# femtoUSB_r1_0_2-rgb.net
KiCad netlist of a schematic drawn in EAGLE
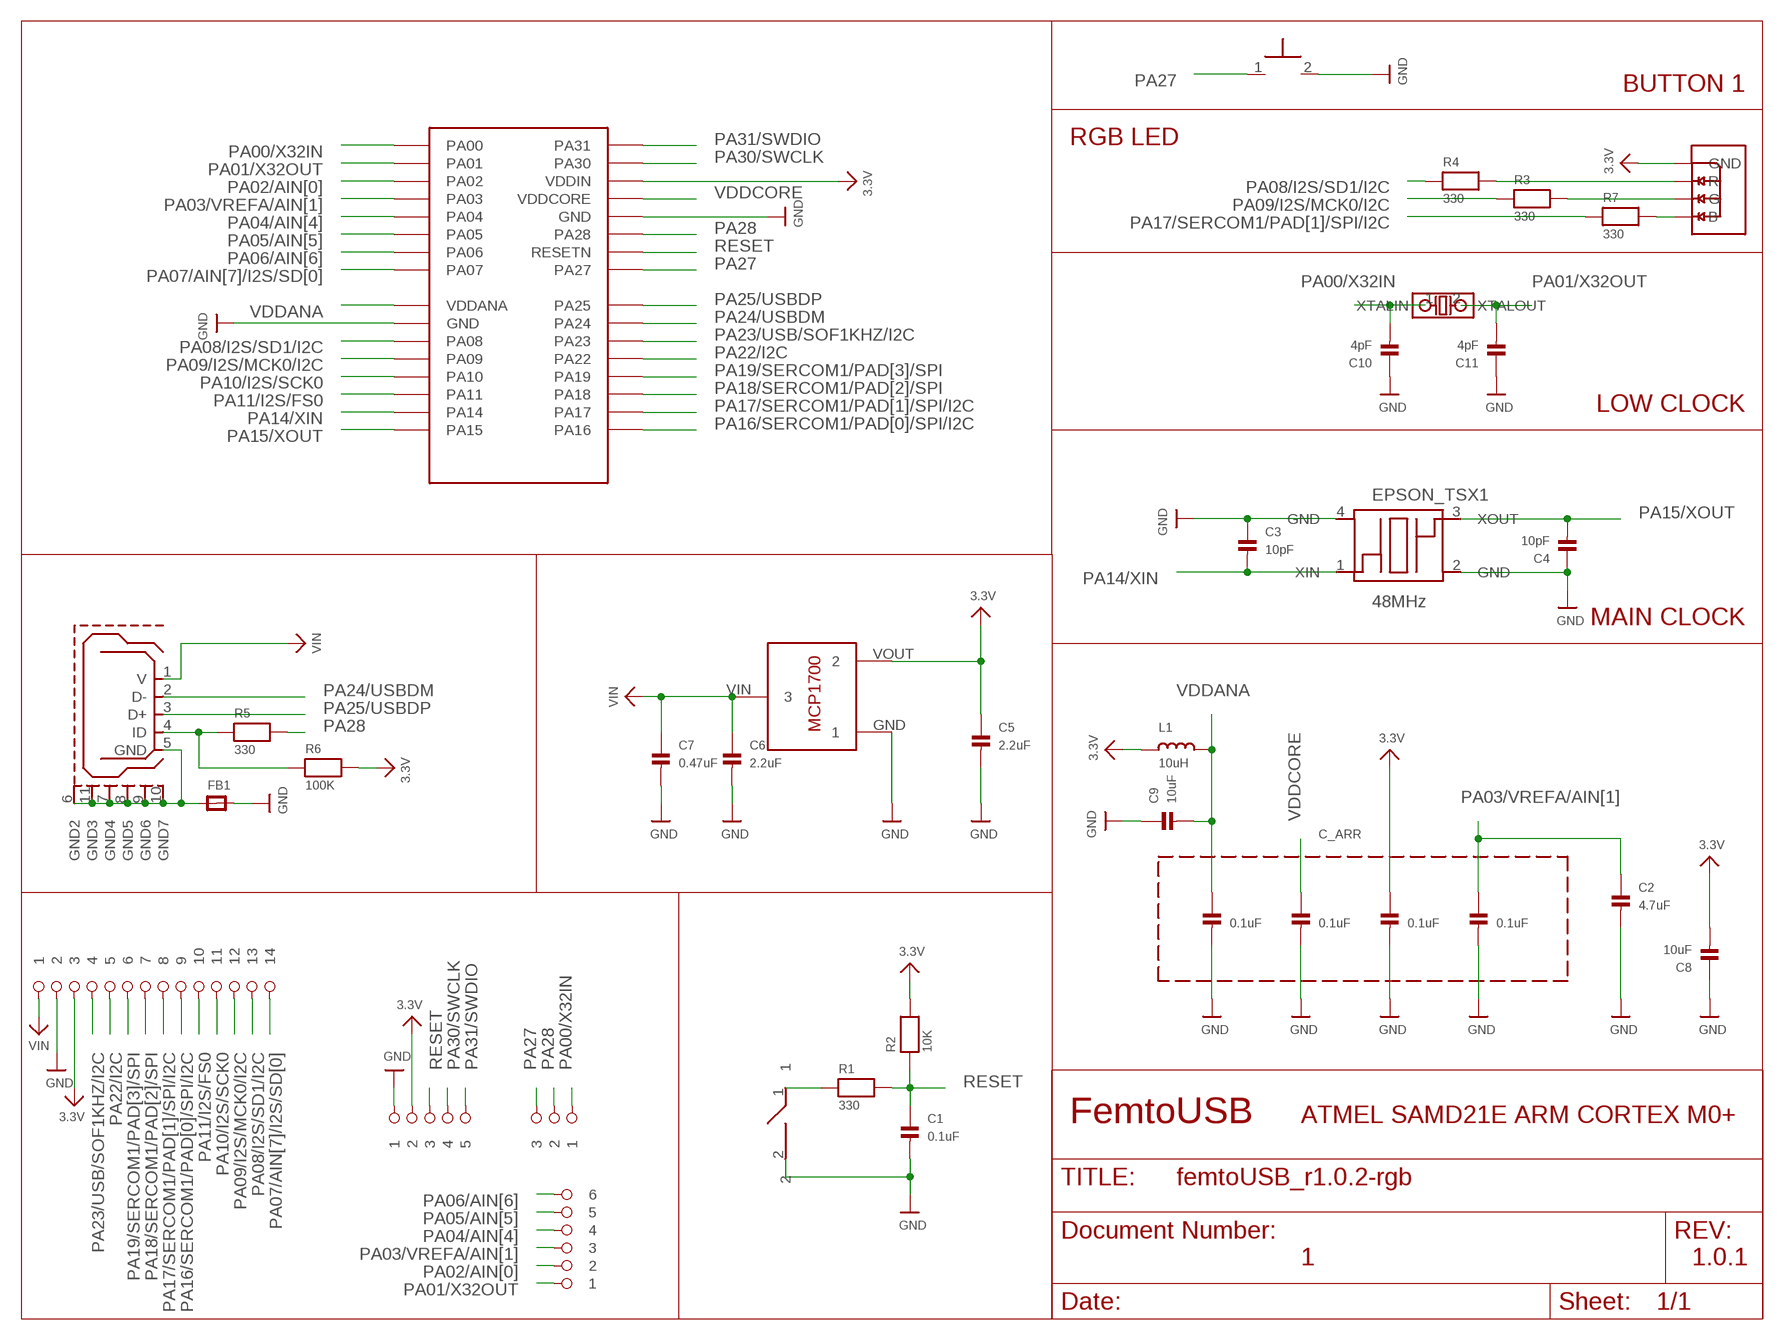
[diagram p0: schematic, sheet 1]

(export (version "E")
  (design (tool "Eeschema 10.0.6"))
  (components
    (comp (ref "BTN_BOOT")
      (value "TACTILE_SWITCH_NO_GND_NO_BOSS")
      (footprint "eagle-import:SIDE_ACT_NO_GND_NO_BOSS")
      (libsource (lib "eagle-import") (part "TACTILE_SWITCH_NO_GND_NO_BOSS"))
    )
    (comp (ref "C1")
      (value "0.1uF")
      (footprint "eagle-import:_0402MP")
      (libsource (lib "eagle-import") (part "CAP_CERAMIC_0402MP"))
    )
    (comp (ref "C2")
      (value "4.7uF")
      (footprint "eagle-import:_0402MP")
      (libsource (lib "eagle-import") (part "CAP_CERAMIC_0402MP"))
    )
    (comp (ref "C3")
      (value "10pF")
      (footprint "eagle-import:_0402MP")
      (libsource (lib "eagle-import") (part "CAP_CERAMIC_0402MP"))
    )
    (comp (ref "C4")
      (value "10pF")
      (footprint "eagle-import:_0402MP")
      (libsource (lib "eagle-import") (part "CAP_CERAMIC_0402MP"))
    )
    (comp (ref "C5")
      (value "2.2uF")
      (footprint "eagle-import:_0402MP")
      (libsource (lib "eagle-import") (part "CAP_CERAMIC_0402MP"))
    )
    (comp (ref "C6")
      (value "2.2uF")
      (footprint "eagle-import:_0402MP")
      (libsource (lib "eagle-import") (part "CAP_CERAMIC_0402MP"))
    )
    (comp (ref "C7")
      (value "0.47uF")
      (footprint "eagle-import:_0402MP")
      (libsource (lib "eagle-import") (part "CAP_CERAMIC_0402MP"))
    )
    (comp (ref "C8")
      (value "10uF")
      (footprint "eagle-import:_0402MP")
      (libsource (lib "eagle-import") (part "CAP_CERAMIC_0402MP"))
    )
    (comp (ref "C9")
      (value "10uF")
      (footprint "eagle-import:_0402MP")
      (libsource (lib "eagle-import") (part "CAP_CERAMIC_0402MP"))
    )
    (comp (ref "C10")
      (value "4pF")
      (footprint "eagle-import:_0402MP")
      (libsource (lib "eagle-import") (part "CAP_CERAMIC_0402MP"))
    )
    (comp (ref "C11")
      (value "4pF")
      (footprint "eagle-import:_0402MP")
      (libsource (lib "eagle-import") (part "CAP_CERAMIC_0402MP"))
    )
    (comp (ref "C_ARR")
      (value "0.1uF")
      (footprint "eagle-import:CAPACITOR_ARRAY_1206_MONO_1X4")
      (libsource (lib "eagle-import") (part "KEMET_CERAMIC_CAPACITOR_ARRAY_1X4"))
    )
    (comp (ref "EPSON_TSX1")
      (value "48MHz")
      (footprint "eagle-import:TSX-3225")
      (libsource (lib "eagle-import") (part "TSX-3225"))
    )
    (comp (ref "FB1")
      (value "FERRITE_0603MP")
      (footprint "eagle-import:_0603MP")
      (libsource (lib "eagle-import") (part "FERRITE_0603MP"))
    )
    (comp (ref "IC1")
      (value "ATSAMD21E18A-MUT")
      (footprint "eagle-import:QFN32")
      (libsource (lib "eagle-import") (part "ATSAMD21E18A-MUT"))
    )
    (comp (ref "L1")
      (value "10uH")
      (footprint "eagle-import:_0603MP")
      (libsource (lib "eagle-import") (part "INDUCTOR_0603MP"))
    )
    (comp (ref "LDO_VREG")
      (value "MCP1700T-3302E/TT")
      (footprint "eagle-import:MCP1700T-3302E_TT")
      (libsource (lib "eagle-import") (part "MCP1700T-3302E/TT"))
    )
    (comp (ref "MICRO_B_USB")
      (value "USB_MICROB")
      (footprint "eagle-import:USB_MICROB_PACKAGE")
      (libsource (lib "eagle-import") (part "USB_MICROB"))
    )
    (comp (ref "OSC32K")
      (value "ABS06-107-32.768KHZ-T")
      (footprint "eagle-import:ABS06-107-32.768KHZ-T")
      (libsource (lib "eagle-import") (part "ABS06-107-32.768KHZ-T"))
    )
    (comp (ref "PIN_1X3")
      (value "1X3_ROUND")
      (footprint "eagle-import:1X3_ROUND")
      (libsource (lib "eagle-import") (part "1X3_ROUND"))
    )
    (comp (ref "PIN_1X5")
      (value "1X5_ROUND")
      (footprint "eagle-import:1X5_ROUND")
      (libsource (lib "eagle-import") (part "1X5_ROUND"))
    )
    (comp (ref "PIN_1X6")
      (value "1X6_ROUND")
      (footprint "eagle-import:1X6_ROUND")
      (libsource (lib "eagle-import") (part "1X6_ROUND"))
    )
    (comp (ref "PIN_1X14")
      (value "1X14_ROUND")
      (footprint "eagle-import:1X14_ROUND")
      (libsource (lib "eagle-import") (part "1X14_ROUND"))
    )
    (comp (ref "R1")
      (value "330")
      (footprint "eagle-import:_0402MP")
      (libsource (lib "eagle-import") (part "RESISTOR_0402MP"))
    )
    (comp (ref "R2")
      (value "10K")
      (footprint "eagle-import:_0402MP")
      (libsource (lib "eagle-import") (part "RESISTOR_0402MP"))
    )
    (comp (ref "R3")
      (value "330")
      (footprint "eagle-import:_0402MP")
      (libsource (lib "eagle-import") (part "RESISTOR_0402MP"))
    )
    (comp (ref "R4")
      (value "330")
      (footprint "eagle-import:_0402MP")
      (libsource (lib "eagle-import") (part "RESISTOR_0402MP"))
    )
    (comp (ref "R5")
      (value "330")
      (footprint "eagle-import:_0402MP")
      (libsource (lib "eagle-import") (part "RESISTOR_0402MP"))
    )
    (comp (ref "R6")
      (value "100K")
      (footprint "eagle-import:_0402MP")
      (libsource (lib "eagle-import") (part "RESISTOR_0402MP"))
    )
    (comp (ref "R7")
      (value "330")
      (footprint "eagle-import:_0402MP")
      (libsource (lib "eagle-import") (part "RESISTOR_0402MP"))
    )
    (comp (ref "RGBLED")
      (value "LRTB_R48G")
      (footprint "eagle-import:LRTB_R48G")
      (libsource (lib "eagle-import") (part "LRTB_R48G"))
    )
    (comp (ref "SJ_RESET")
      (value "SPST_SMD")
      (footprint "eagle-import:SPST_SMD")
      (libsource (lib "eagle-import") (part "SPST_SMD"))
    )
  )
  (nets
    (net (code "1") (name "/PA00{slash}X32IN") (class "Default")
      (node (ref "C10") (pin "2") (pinfunction "P$2_2") (pintype "passive"))
      (node (ref "IC1") (pin "1") (pinfunction "PA00_1") (pintype "bidirectional"))
      (node (ref "OSC32K") (pin "1") (pinfunction "XTALIN_1") (pintype "bidirectional"))
      (node (ref "PIN_1X3") (pin "P$1") (pinfunction "1_P$1") (pintype "bidirectional"))
    )
    (net (code "2") (name "/PA01{slash}X32OUT") (class "Default")
      (node (ref "C11") (pin "2") (pinfunction "P$2_2") (pintype "passive"))
      (node (ref "IC1") (pin "2") (pinfunction "PA01_2") (pintype "bidirectional"))
      (node (ref "OSC32K") (pin "2") (pinfunction "XTALOUT_2") (pintype "bidirectional"))
      (node (ref "PIN_1X6") (pin "P$1") (pinfunction "1_P$1") (pintype "bidirectional"))
    )
    (net (code "3") (name "/PA02{slash}AIN[0]") (class "Default")
      (node (ref "IC1") (pin "3") (pinfunction "PA02_3") (pintype "bidirectional"))
      (node (ref "PIN_1X6") (pin "P$2") (pinfunction "2_P$2") (pintype "bidirectional"))
    )
    (net (code "4") (name "/PA03{slash}VREFA{slash}AIN[1]") (class "Default")
      (node (ref "C2") (pin "1") (pinfunction "P$1_1") (pintype "passive"))
      (node (ref "C_ARR") (pin "7") (pinfunction "P$7_7") (pintype "passive"))
      (node (ref "IC1") (pin "4") (pinfunction "PA03_4") (pintype "bidirectional"))
      (node (ref "PIN_1X6") (pin "P$3") (pinfunction "3_P$3") (pintype "bidirectional"))
    )
    (net (code "5") (name "/PA04{slash}AIN[4]") (class "Default")
      (node (ref "IC1") (pin "5") (pinfunction "PA04_5") (pintype "bidirectional"))
      (node (ref "PIN_1X6") (pin "P$4") (pinfunction "4_P$4") (pintype "bidirectional"))
    )
    (net (code "6") (name "/PA05{slash}AIN[5]") (class "Default")
      (node (ref "IC1") (pin "6") (pinfunction "PA05_6") (pintype "bidirectional"))
      (node (ref "PIN_1X6") (pin "P$5") (pinfunction "5_P$5") (pintype "bidirectional"))
    )
    (net (code "7") (name "/PA06{slash}AIN[6]") (class "Default")
      (node (ref "IC1") (pin "7") (pinfunction "PA06_7") (pintype "bidirectional"))
      (node (ref "PIN_1X6") (pin "P$6") (pinfunction "6_P$6") (pintype "bidirectional"))
    )
    (net (code "8") (name "/PA07{slash}AIN[7]{slash}I2S{slash}SD[0]") (class "Default")
      (node (ref "IC1") (pin "8") (pinfunction "PA07_8") (pintype "bidirectional"))
      (node (ref "PIN_1X14") (pin "P$14") (pinfunction "14_P$14") (pintype "bidirectional"))
    )
    (net (code "9") (name "/PA08{slash}I2S{slash}SD1{slash}I2C") (class "Default")
      (node (ref "IC1") (pin "11") (pinfunction "PA08_11") (pintype "bidirectional"))
      (node (ref "PIN_1X14") (pin "P$13") (pinfunction "13_P$13") (pintype "bidirectional"))
      (node (ref "R4") (pin "1") (pinfunction "1_1") (pintype "passive"))
    )
    (net (code "10") (name "/PA09{slash}I2S{slash}MCK0{slash}I2C") (class "Default")
      (node (ref "IC1") (pin "12") (pinfunction "PA09_12") (pintype "bidirectional"))
      (node (ref "PIN_1X14") (pin "P$12") (pinfunction "12_P$12") (pintype "bidirectional"))
      (node (ref "R3") (pin "1") (pinfunction "1_1") (pintype "passive"))
    )
    (net (code "11") (name "/PA10{slash}I2S{slash}SCK0") (class "Default")
      (node (ref "IC1") (pin "13") (pinfunction "PA10_13") (pintype "bidirectional"))
      (node (ref "PIN_1X14") (pin "P$11") (pinfunction "11_P$11") (pintype "bidirectional"))
    )
    (net (code "12") (name "/PA11{slash}I2S{slash}FS0") (class "Default")
      (node (ref "IC1") (pin "14") (pinfunction "PA11_14") (pintype "bidirectional"))
      (node (ref "PIN_1X14") (pin "P$10") (pinfunction "10_P$10") (pintype "bidirectional"))
    )
    (net (code "13") (name "/PA14{slash}XIN") (class "Default")
      (node (ref "C3") (pin "2") (pinfunction "P$2_2") (pintype "passive"))
      (node (ref "EPSON_TSX1") (pin "1") (pinfunction "XIN_1") (pintype "bidirectional"))
      (node (ref "IC1") (pin "15") (pinfunction "PA14_15") (pintype "bidirectional"))
    )
    (net (code "14") (name "/PA15{slash}XOUT") (class "Default")
      (node (ref "C4") (pin "2") (pinfunction "P$2_2") (pintype "passive"))
      (node (ref "EPSON_TSX1") (pin "3") (pinfunction "XOUT_3") (pintype "bidirectional"))
      (node (ref "IC1") (pin "16") (pinfunction "PA15_16") (pintype "bidirectional"))
    )
    (net (code "15") (name "/PA16{slash}SERCOM1{slash}PAD[0]{slash}SPI{slash}I2C") (class "Default")
      (node (ref "IC1") (pin "17") (pinfunction "PA16_17") (pintype "bidirectional"))
      (node (ref "PIN_1X14") (pin "P$9") (pinfunction "9_P$9") (pintype "bidirectional"))
    )
    (net (code "16") (name "/PA17{slash}SERCOM1{slash}PAD[1]{slash}SPI{slash}I2C") (class "Default")
      (node (ref "IC1") (pin "18") (pinfunction "PA17_18") (pintype "bidirectional"))
      (node (ref "PIN_1X14") (pin "P$8") (pinfunction "8_P$8") (pintype "bidirectional"))
      (node (ref "R7") (pin "1") (pinfunction "1_1") (pintype "passive"))
    )
    (net (code "17") (name "/PA18{slash}SERCOM1{slash}PAD[2]{slash}SPI") (class "Default")
      (node (ref "IC1") (pin "19") (pinfunction "PA18_19") (pintype "bidirectional"))
      (node (ref "PIN_1X14") (pin "P$7") (pinfunction "7_P$7") (pintype "bidirectional"))
    )
    (net (code "18") (name "/PA19{slash}SERCOM1{slash}PAD[3]{slash}SPI") (class "Default")
      (node (ref "IC1") (pin "20") (pinfunction "PA19_20") (pintype "bidirectional"))
      (node (ref "PIN_1X14") (pin "P$6") (pinfunction "6_P$6") (pintype "bidirectional"))
    )
    (net (code "19") (name "/PA22{slash}I2C") (class "Default")
      (node (ref "IC1") (pin "21") (pinfunction "PA22_21") (pintype "bidirectional"))
      (node (ref "PIN_1X14") (pin "P$5") (pinfunction "5_P$5") (pintype "bidirectional"))
    )
    (net (code "20") (name "/PA23{slash}USB{slash}SOF1KHZ{slash}I2C") (class "Default")
      (node (ref "IC1") (pin "22") (pinfunction "PA23_22") (pintype "bidirectional"))
      (node (ref "PIN_1X14") (pin "P$4") (pinfunction "4_P$4") (pintype "bidirectional"))
    )
    (net (code "21") (name "/PA24{slash}USBDM") (class "Default")
      (node (ref "IC1") (pin "23") (pinfunction "PA24_23") (pintype "bidirectional"))
      (node (ref "MICRO_B_USB") (pin "2") (pinfunction "D-_2") (pintype "bidirectional"))
    )
    (net (code "22") (name "/PA25{slash}USBDP") (class "Default")
      (node (ref "IC1") (pin "24") (pinfunction "PA25_24") (pintype "bidirectional"))
      (node (ref "MICRO_B_USB") (pin "3") (pinfunction "D+_3") (pintype "bidirectional"))
    )
    (net (code "23") (name "/PA27") (class "Default")
      (node (ref "BTN_BOOT") (pin "1") (pinfunction "1_1") (pintype "bidirectional"))
      (node (ref "IC1") (pin "25") (pinfunction "PA27_25") (pintype "bidirectional"))
      (node (ref "PIN_1X3") (pin "P$3") (pinfunction "3_P$3") (pintype "bidirectional"))
    )
    (net (code "24") (name "/PA28") (class "Default")
      (node (ref "IC1") (pin "27") (pinfunction "PA28_27") (pintype "bidirectional"))
      (node (ref "PIN_1X3") (pin "P$2") (pinfunction "2_P$2") (pintype "bidirectional"))
      (node (ref "R5") (pin "2") (pinfunction "2_2") (pintype "passive"))
    )
    (net (code "25") (name "/PA30{slash}SWCLK") (class "Default")
      (node (ref "IC1") (pin "31") (pinfunction "PA30_31") (pintype "bidirectional"))
      (node (ref "PIN_1X5") (pin "P$4") (pinfunction "4_P$4") (pintype "bidirectional"))
    )
    (net (code "26") (name "/PA31{slash}SWDIO") (class "Default")
      (node (ref "IC1") (pin "32") (pinfunction "PA31_32") (pintype "bidirectional"))
      (node (ref "PIN_1X5") (pin "P$5") (pinfunction "5_P$5") (pintype "bidirectional"))
    )
    (net (code "27") (name "/RESET") (class "Default")
      (node (ref "C1") (pin "1") (pinfunction "P$1_1") (pintype "passive"))
      (node (ref "IC1") (pin "26") (pinfunction "RESETN_26") (pintype "bidirectional"))
      (node (ref "PIN_1X5") (pin "P$3") (pinfunction "3_P$3") (pintype "bidirectional"))
      (node (ref "R1") (pin "2") (pinfunction "2_2") (pintype "passive"))
      (node (ref "R2") (pin "1") (pinfunction "1_1") (pintype "passive"))
    )
    (net (code "28") (name "/VDDANA") (class "Default")
      (node (ref "C9") (pin "2") (pinfunction "P$2_2") (pintype "passive"))
      (node (ref "C_ARR") (pin "1") (pinfunction "P$1_1") (pintype "passive"))
      (node (ref "IC1") (pin "9") (pinfunction "VDDANA_9") (pintype "bidirectional"))
      (node (ref "L1") (pin "2") (pinfunction "2_2") (pintype "passive"))
    )
    (net (code "29") (name "/VDDCORE") (class "Default")
      (node (ref "C_ARR") (pin "3") (pinfunction "P$3_3") (pintype "passive"))
      (node (ref "IC1") (pin "29") (pinfunction "VDDCORE_29") (pintype "bidirectional"))
    )
    (net (code "30") (name "3.3V") (class "Default")
      (node (ref "C5") (pin "1") (pinfunction "P$1_1") (pintype "passive"))
      (node (ref "C8") (pin "2") (pinfunction "P$2_2") (pintype "passive"))
      (node (ref "C_ARR") (pin "5") (pinfunction "P$5_5") (pintype "passive"))
      (node (ref "IC1") (pin "30") (pinfunction "VDDIN_30") (pintype "bidirectional"))
      (node (ref "L1") (pin "1") (pinfunction "1_1") (pintype "passive"))
      (node (ref "LDO_VREG") (pin "VOUT") (pinfunction "2_VOUT") (pintype "bidirectional"))
      (node (ref "PIN_1X14") (pin "P$3") (pinfunction "3_P$3") (pintype "bidirectional"))
      (node (ref "PIN_1X5") (pin "P$2") (pinfunction "2_P$2") (pintype "bidirectional"))
      (node (ref "R2") (pin "2") (pinfunction "2_2") (pintype "passive"))
      (node (ref "R6") (pin "2") (pinfunction "2_2") (pintype "passive"))
      (node (ref "RGBLED") (pin "1") (pinfunction "GND_1") (pintype "bidirectional"))
    )
    (net (code "31") (name "GND") (class "Default")
      (node (ref "BTN_BOOT") (pin "2") (pinfunction "2_2") (pintype "bidirectional"))
      (node (ref "C1") (pin "2") (pinfunction "P$2_2") (pintype "passive"))
      (node (ref "C10") (pin "1") (pinfunction "P$1_1") (pintype "passive"))
      (node (ref "C11") (pin "1") (pinfunction "P$1_1") (pintype "passive"))
      (node (ref "C2") (pin "2") (pinfunction "P$2_2") (pintype "passive"))
      (node (ref "C3") (pin "1") (pinfunction "P$1_1") (pintype "passive"))
      (node (ref "C4") (pin "1") (pinfunction "P$1_1") (pintype "passive"))
      (node (ref "C5") (pin "2") (pinfunction "P$2_2") (pintype "passive"))
      (node (ref "C6") (pin "2") (pinfunction "P$2_2") (pintype "passive"))
      (node (ref "C7") (pin "2") (pinfunction "P$2_2") (pintype "passive"))
      (node (ref "C8") (pin "1") (pinfunction "P$1_1") (pintype "passive"))
      (node (ref "C9") (pin "1") (pinfunction "P$1_1") (pintype "passive"))
      (node (ref "C_ARR") (pin "2") (pinfunction "P$2_2") (pintype "passive"))
      (node (ref "C_ARR") (pin "4") (pinfunction "P$4_4") (pintype "passive"))
      (node (ref "C_ARR") (pin "6") (pinfunction "P$6_6") (pintype "passive"))
      (node (ref "C_ARR") (pin "8") (pinfunction "P$8_8") (pintype "passive"))
      (node (ref "EPSON_TSX1") (pin "2") (pinfunction "GND_2") (pintype "bidirectional"))
      (node (ref "EPSON_TSX1") (pin "4") (pinfunction "GND_4") (pintype "bidirectional"))
      (node (ref "FB1") (pin "2") (pinfunction "P$2_2") (pintype "passive"))
      (node (ref "IC1") (pin "10") (pinfunction "GND_10") (pintype "bidirectional"))
      (node (ref "IC1") (pin "28") (pinfunction "GND_28") (pintype "bidirectional"))
      (node (ref "LDO_VREG") (pin "GND") (pinfunction "1_GND") (pintype "bidirectional"))
      (node (ref "PIN_1X14") (pin "P$2") (pinfunction "2_P$2") (pintype "bidirectional"))
      (node (ref "PIN_1X5") (pin "P$1") (pinfunction "1_P$1") (pintype "bidirectional"))
      (node (ref "SJ_RESET") (pin "2") (pinfunction "2_2") (pintype "bidirectional"))
    )
    (net (code "32") (name "Net-(FB1-P$1)") (class "Default")
      (node (ref "FB1") (pin "1") (pinfunction "P$1_1") (pintype "passive"))
      (node (ref "MICRO_B_USB") (pin "10") (pinfunction "GND7_10") (pintype "bidirectional"))
      (node (ref "MICRO_B_USB") (pin "11") (pinfunction "GND3_11") (pintype "bidirectional"))
      (node (ref "MICRO_B_USB") (pin "5") (pinfunction "GND_5") (pintype "bidirectional"))
      (node (ref "MICRO_B_USB") (pin "6") (pinfunction "GND2_6") (pintype "bidirectional"))
      (node (ref "MICRO_B_USB") (pin "7") (pinfunction "GND4_7") (pintype "bidirectional"))
      (node (ref "MICRO_B_USB") (pin "8") (pinfunction "GND5_8") (pintype "bidirectional"))
      (node (ref "MICRO_B_USB") (pin "9") (pinfunction "GND6_9") (pintype "bidirectional"))
    )
    (net (code "33") (name "Net-(MICRO_B_USB-ID)") (class "Default")
      (node (ref "MICRO_B_USB") (pin "4") (pinfunction "ID_4") (pintype "bidirectional"))
      (node (ref "R5") (pin "1") (pinfunction "1_1") (pintype "passive"))
      (node (ref "R6") (pin "1") (pinfunction "1_1") (pintype "passive"))
    )
    (net (code "34") (name "Net-(R1-Pad1)") (class "Default")
      (node (ref "R1") (pin "1") (pinfunction "1_1") (pintype "passive"))
      (node (ref "SJ_RESET") (pin "1") (pinfunction "1_1") (pintype "bidirectional"))
    )
    (net (code "35") (name "Net-(RGBLED-B)") (class "Default")
      (node (ref "R7") (pin "2") (pinfunction "2_2") (pintype "passive"))
      (node (ref "RGBLED") (pin "4") (pinfunction "B_4") (pintype "bidirectional"))
    )
    (net (code "36") (name "Net-(RGBLED-G)") (class "Default")
      (node (ref "R3") (pin "2") (pinfunction "2_2") (pintype "passive"))
      (node (ref "RGBLED") (pin "3") (pinfunction "G_3") (pintype "bidirectional"))
    )
    (net (code "37") (name "Net-(RGBLED-R)") (class "Default")
      (node (ref "R4") (pin "2") (pinfunction "2_2") (pintype "passive"))
      (node (ref "RGBLED") (pin "2") (pinfunction "R_2") (pintype "bidirectional"))
    )
    (net (code "38") (name "VIN") (class "Default")
      (node (ref "C6") (pin "1") (pinfunction "P$1_1") (pintype "passive"))
      (node (ref "C7") (pin "1") (pinfunction "P$1_1") (pintype "passive"))
      (node (ref "LDO_VREG") (pin "VIN") (pinfunction "3_VIN") (pintype "bidirectional"))
      (node (ref "MICRO_B_USB") (pin "1") (pinfunction "V_1") (pintype "bidirectional"))
      (node (ref "PIN_1X14") (pin "P$1") (pinfunction "1_P$1") (pintype "bidirectional"))
    )
  )
)
